# single_layer.net
KiCad netlist of a schematic drawn in Altium Designer
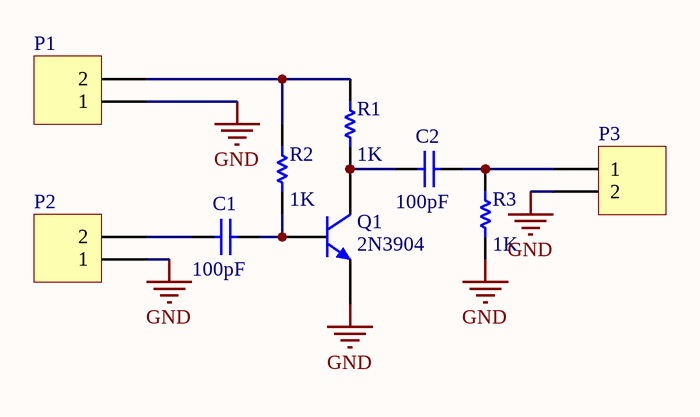
[diagram p0: single_layer.SchDoc]

(export (version "E")
  (design (tool "Eeschema 10.0.6"))
  (components
    (comp (ref "C1")
      (value "100pF")
      (footprint "RAD-0.1")
      (description "Capacitor")
      (fields (field (name "Comment") "Cap") (field (name "PUBLISHER") "Altium Limited"))
      (libsource (lib "Miscellaneous Devices") (part "Cap"))
    )
    (comp (ref "C2")
      (value "100pF")
      (footprint "RAD-0.1")
      (description "Capacitor")
      (fields (field (name "Comment") "Cap") (field (name "PUBLISHER") "Altium Limited"))
      (libsource (lib "Miscellaneous Devices") (part "Cap"))
    )
    (comp (ref "P1")
      (value "Header 2")
      (footprint "HDR1X2")
      (description "Header, 2-Pin")
      (fields (field (name "PUBLISHER") "Altium Limited"))
      (libsource (lib "Miscellaneous Connectors") (part "Header 2"))
    )
    (comp (ref "P2")
      (value "Header 2")
      (footprint "HDR1X2")
      (description "Header, 2-Pin")
      (fields (field (name "PUBLISHER") "Altium Limited"))
      (libsource (lib "Miscellaneous Connectors") (part "Header 2"))
    )
    (comp (ref "P3")
      (value "Header 2")
      (footprint "HDR1X2")
      (description "Header, 2-Pin")
      (fields (field (name "PUBLISHER") "Altium Limited"))
      (libsource (lib "") (part "Header 2_1"))
    )
    (comp (ref "Q1")
      (value "2N3904")
      (footprint "BCY-W3/E4")
      (description "NPN General Purpose Amplifier")
      (fields (field (name "PUBLISHER") "Altium Limited"))
      (libsource (lib "Miscellaneous Devices") (part "2N3904"))
    )
    (comp (ref "R1")
      (value "1K")
      (footprint "AXIAL-0.3")
      (description "Resistor")
      (fields (field (name "Comment") "Res1") (field (name "PUBLISHER") "Altium Limited"))
      (libsource (lib "Miscellaneous Devices") (part "Res1"))
    )
    (comp (ref "R2")
      (value "1K")
      (footprint "AXIAL-0.3")
      (description "Resistor")
      (fields (field (name "Comment") "Res1") (field (name "PUBLISHER") "Altium Limited"))
      (libsource (lib "Miscellaneous Devices") (part "Res1"))
    )
    (comp (ref "R3")
      (value "1K")
      (footprint "AXIAL-0.3")
      (description "Resistor")
      (fields (field (name "Comment") "Res1") (field (name "PUBLISHER") "Altium Limited"))
      (libsource (lib "Miscellaneous Devices") (part "Res1"))
    )
  )
  (nets
    (net (code "1") (name "GND") (class "Default")
      (node (ref "P1") (pin "1") (pinfunction "1_1") (pintype "passive"))
      (node (ref "P2") (pin "1") (pinfunction "1_1") (pintype "passive"))
      (node (ref "P3") (pin "2") (pinfunction "2_2") (pintype "passive"))
      (node (ref "Q1") (pin "1") (pinfunction "E_1") (pintype "passive"))
      (node (ref "R3") (pin "1") (pinfunction "1_1") (pintype "passive"))
    )
    (net (code "2") (name "Net-(C1-Pad1)") (class "Default")
      (node (ref "C1") (pin "1") (pinfunction "1_1") (pintype "passive"))
      (node (ref "P2") (pin "2") (pinfunction "2_2") (pintype "passive"))
    )
    (net (code "3") (name "Net-(C2-Pad2)") (class "Default")
      (node (ref "C2") (pin "2") (pinfunction "2_2") (pintype "passive"))
      (node (ref "P3") (pin "1") (pinfunction "1_1") (pintype "passive"))
      (node (ref "R3") (pin "2") (pinfunction "2_2") (pintype "passive"))
    )
    (net (code "4") (name "Net-(P1-Pad2)") (class "Default")
      (node (ref "P1") (pin "2") (pinfunction "2_2") (pintype "passive"))
      (node (ref "R1") (pin "2") (pinfunction "2_2") (pintype "passive"))
      (node (ref "R2") (pin "2") (pinfunction "2_2") (pintype "passive"))
    )
    (net (code "5") (name "Net-(Q1-B)") (class "Default")
      (node (ref "C1") (pin "2") (pinfunction "2_2") (pintype "passive"))
      (node (ref "Q1") (pin "2") (pinfunction "B_2") (pintype "passive"))
      (node (ref "R2") (pin "1") (pinfunction "1_1") (pintype "passive"))
    )
    (net (code "6") (name "Net-(Q1-C)") (class "Default")
      (node (ref "C2") (pin "1") (pinfunction "1_1") (pintype "passive"))
      (node (ref "Q1") (pin "3") (pinfunction "C_3") (pintype "passive"))
      (node (ref "R1") (pin "1") (pinfunction "1_1") (pintype "passive"))
    )
  )
)
